# VoltammCircuit.net
KiCad netlist of a schematic drawn in EAGLE
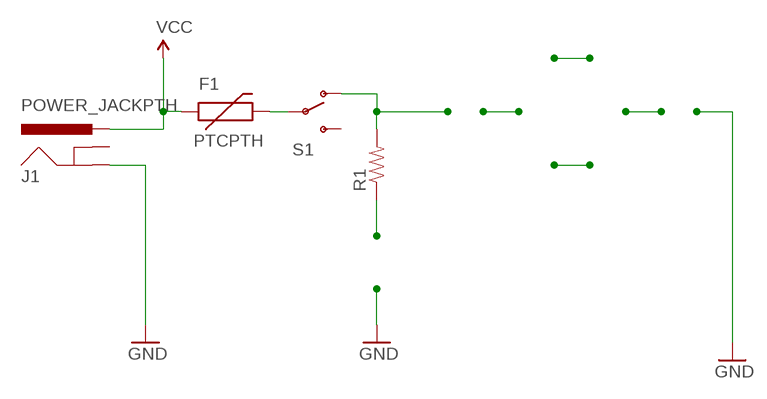
[diagram p0: schematic, sheet 1]

(export (version "E")
  (design (tool "Eeschema 10.0.6"))
  (components
    (comp (ref "F1")
      (value "PTCPTH")
      (footprint "eagle-import:PTC")
      (libsource (lib "eagle-import") (part "PTCPTH"))
    )
    (comp (ref "J1")
      (value "POWER_JACKPTH")
      (footprint "eagle-import:POWER_JACK_PTH")
      (libsource (lib "eagle-import") (part "POWER_JACKPTH"))
    )
    (comp (ref "R1")
      (value "RESISTORAXIAL-0.3")
      (footprint "eagle-import:AXIAL-0.3")
      (libsource (lib "eagle-import") (part "RESISTORAXIAL-0.3"))
    )
    (comp (ref "S1")
      (value "SWITCH-SPSTKIT")
      (footprint "eagle-import:SWITCH-SPDT_KIT")
      (libsource (lib "eagle-import") (part "SWITCH-SPSTKIT"))
    )
  )
  (nets
    (net (code "1") (name "GND") (class "Default")
      (node (ref "J1") (pin "GND") (pinfunction "GND_GND") (pintype "bidirectional"))
    )
    (net (code "2") (name "Net-(F1-2)") (class "Default")
      (node (ref "F1") (pin "P$2") (pinfunction "2_P$2") (pintype "bidirectional"))
      (node (ref "S1") (pin "2") (pinfunction "P_2") (pintype "passive"))
    )
    (net (code "3") (name "Net-(R1-2)") (class "Default")
      (node (ref "R1") (pin "P$2") (pinfunction "2_P$2") (pintype "passive"))
      (node (ref "S1") (pin "1") (pinfunction "O_1") (pintype "passive"))
    )
    (net (code "4") (name "VCC") (class "Default")
      (node (ref "F1") (pin "P$1") (pinfunction "1_P$1") (pintype "bidirectional"))
      (node (ref "J1") (pin "PWR") (pinfunction "PWR_PWR") (pintype "bidirectional"))
    )
    (net (code "5") (name "unconnected-(J1-PadGNDBREAK)") (class "Default")
      (node (ref "J1") (pin "GNDBREAK") (pinfunction "GNDBREAK_GNDBREAK") (pintype "bidirectional"))
    )
    (net (code "6") (name "unconnected-(R1-1-PadP$1)") (class "Default")
      (node (ref "R1") (pin "P$1") (pinfunction "1_P$1") (pintype "passive"))
    )
    (net (code "7") (name "unconnected-(S1-S-Pad3)") (class "Default")
      (node (ref "S1") (pin "3") (pinfunction "S_3") (pintype "passive"))
    )
  )
)
